# arduinoFMShield.net
KiCad netlist of a schematic drawn in EAGLE
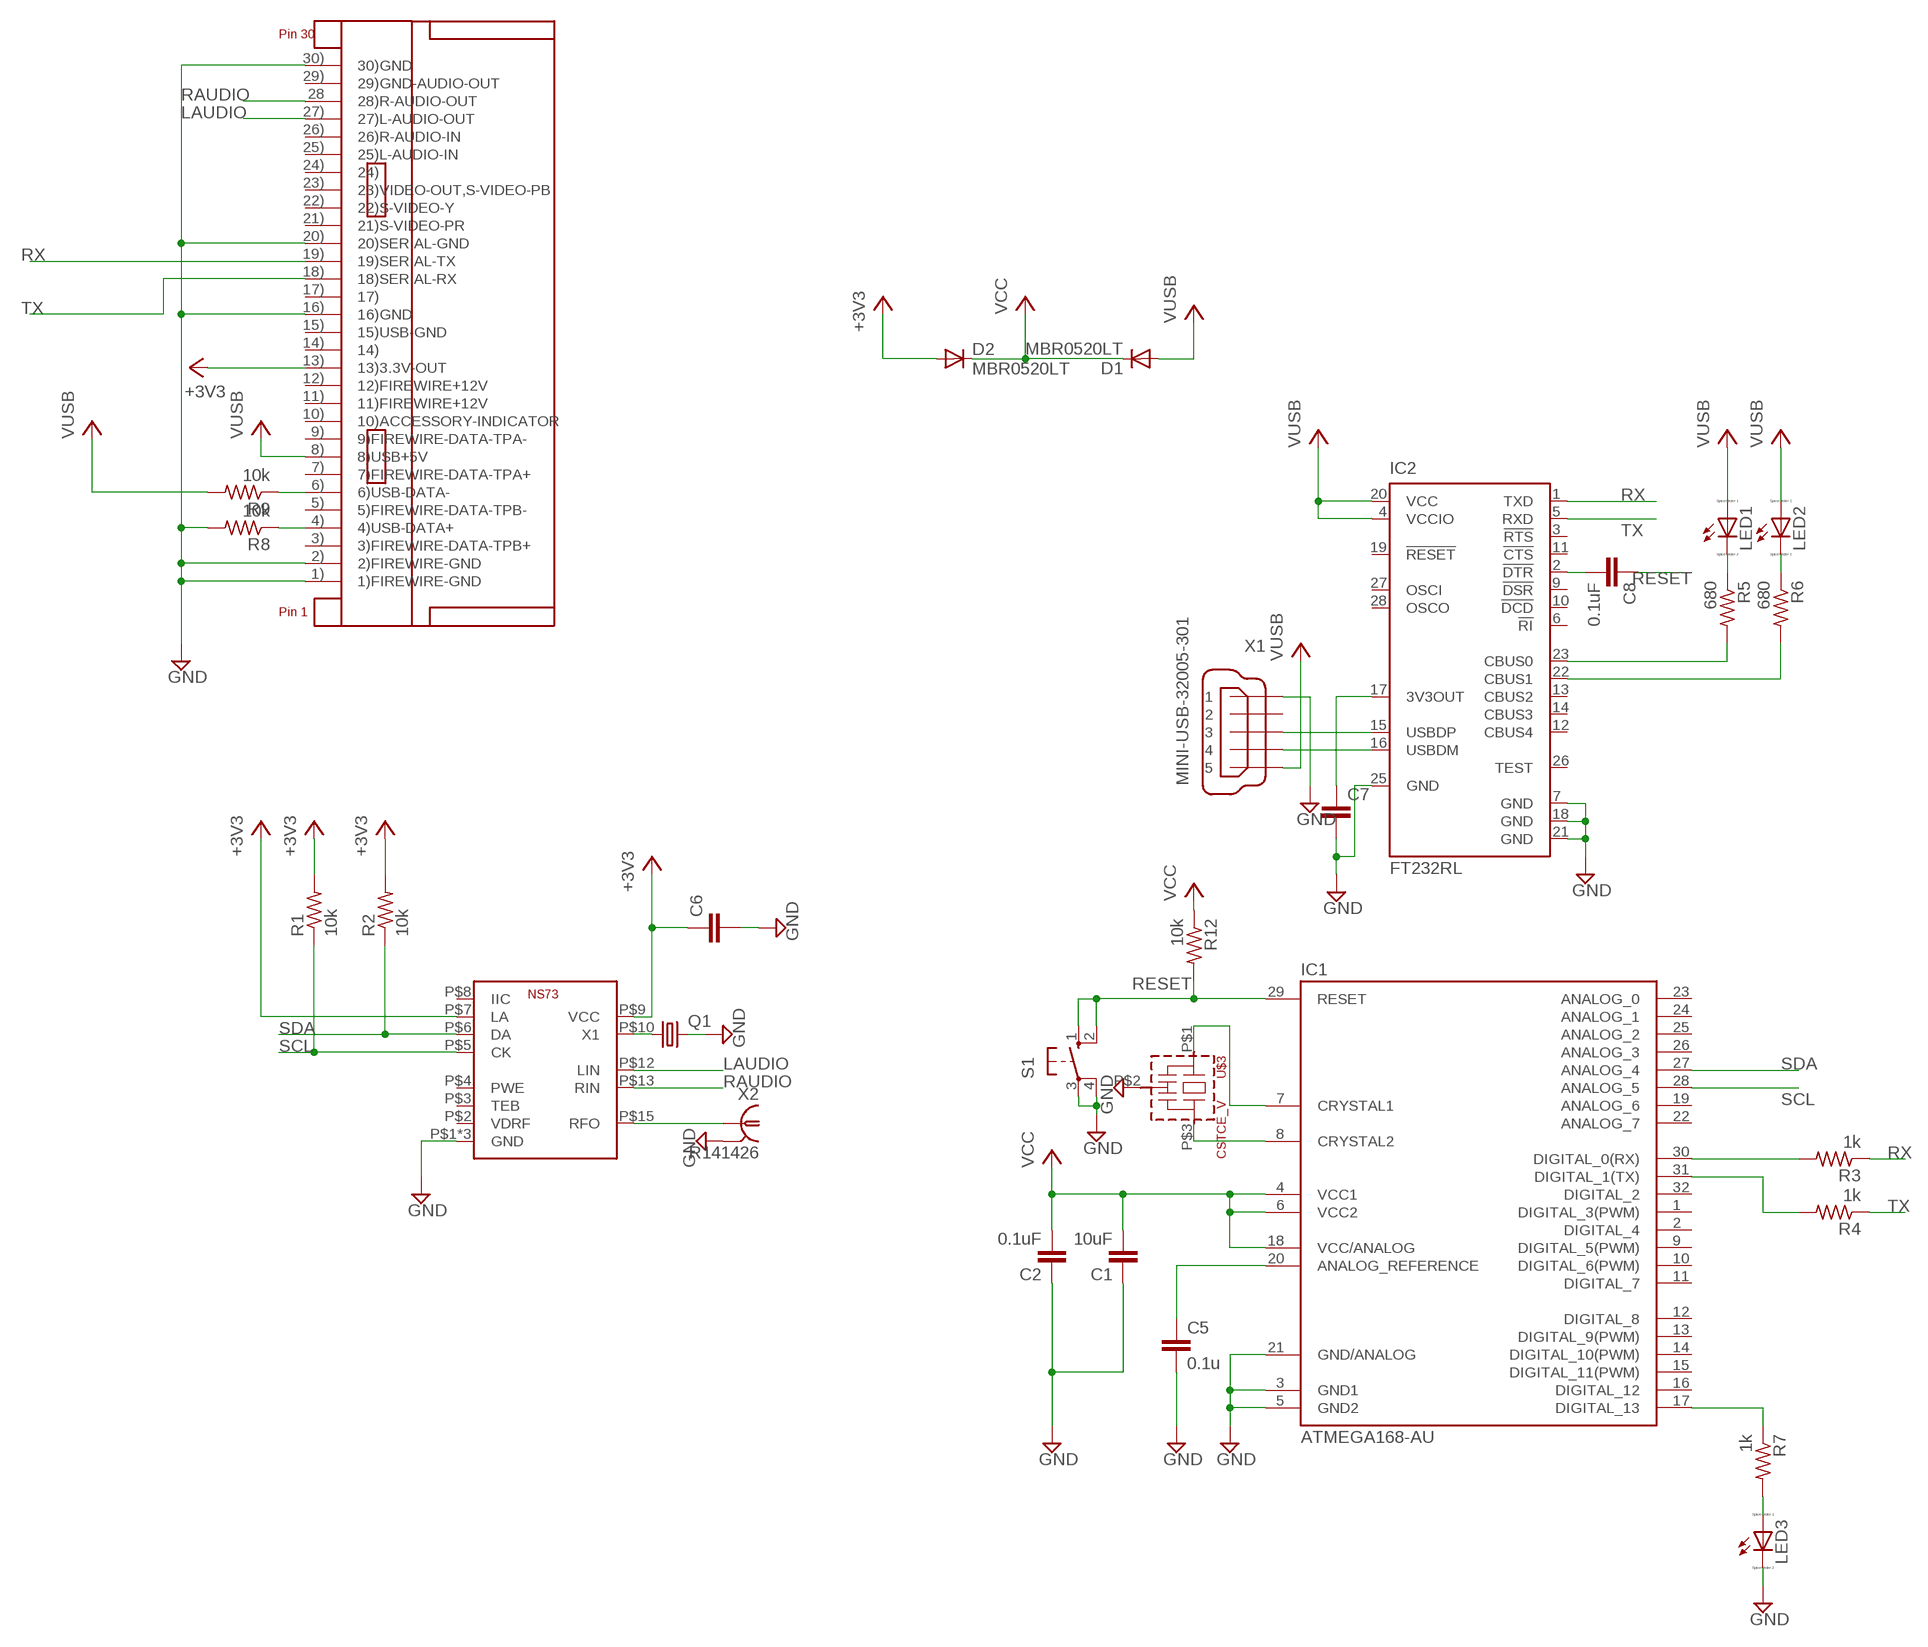
[diagram p0: schematic, sheet 1]

(export (version "E")
  (design (tool "Eeschema 10.0.6"))
  (components
    (comp (ref "C1")
      (value "10uF")
      (footprint "eagle-import:C1206")
      (libsource (lib "eagle-import") (part "C-EUC1206"))
    )
    (comp (ref "C2")
      (value "0.1uF")
      (footprint "eagle-import:C1206")
      (libsource (lib "eagle-import") (part "C-EUC1206"))
    )
    (comp (ref "C5")
      (value "0.1u")
      (footprint "eagle-import:C1206")
      (libsource (lib "eagle-import") (part "C-EUC1206"))
    )
    (comp (ref "C6")
      (value "C-EUC1206")
      (footprint "eagle-import:C1206")
      (libsource (lib "eagle-import") (part "C-EUC1206"))
    )
    (comp (ref "C7")
      (value "C-EUC1206")
      (footprint "eagle-import:C1206")
      (libsource (lib "eagle-import") (part "C-EUC1206"))
    )
    (comp (ref "C8")
      (value "0.1uF")
      (footprint "eagle-import:C1206")
      (libsource (lib "eagle-import") (part "C-EUC1206"))
    )
    (comp (ref "D1")
      (value "MBR0520LT")
      (footprint "eagle-import:SOD123")
      (libsource (lib "eagle-import") (part "MBR0520LT"))
    )
    (comp (ref "D2")
      (value "MBR0520LT")
      (footprint "eagle-import:SOD123")
      (libsource (lib "eagle-import") (part "MBR0520LT"))
    )
    (comp (ref "IC1")
      (value "ATMEGA168-AU")
      (footprint "eagle-import:TQFP32-08")
      (libsource (lib "eagle-import") (part "ATMEGA168-AU"))
    )
    (comp (ref "IC2")
      (value "FT232RL")
      (footprint "eagle-import:SSOP28")
      (libsource (lib "eagle-import") (part "FT232RL"))
    )
    (comp (ref "LED1")
      (value "LED_ESML0603")
      (footprint "eagle-import:LED_SML0603")
      (libsource (lib "eagle-import") (part "LED_ESML0603"))
    )
    (comp (ref "LED2")
      (value "LED_ESML0603")
      (footprint "eagle-import:LED_SML0603")
      (libsource (lib "eagle-import") (part "LED_ESML0603"))
    )
    (comp (ref "LED3")
      (value "LED_ESML0603")
      (footprint "eagle-import:LED_SML0603")
      (libsource (lib "eagle-import") (part "LED_ESML0603"))
    )
    (comp (ref "Q1")
      (value "CRYSTALTC26H")
      (footprint "eagle-import:TC26H")
      (libsource (lib "eagle-import") (part "CRYSTALTC26H"))
    )
    (comp (ref "R1")
      (value "10k")
      (footprint "eagle-import:R1206")
      (libsource (lib "eagle-import") (part "R-US_R1206"))
    )
    (comp (ref "R2")
      (value "10k")
      (footprint "eagle-import:R1206")
      (libsource (lib "eagle-import") (part "R-US_R1206"))
    )
    (comp (ref "R3")
      (value "1k")
      (footprint "eagle-import:R1206")
      (libsource (lib "eagle-import") (part "R-US_R1206"))
    )
    (comp (ref "R4")
      (value "1k")
      (footprint "eagle-import:R1206")
      (libsource (lib "eagle-import") (part "R-US_R1206"))
    )
    (comp (ref "R5")
      (value "680")
      (footprint "eagle-import:R0805")
      (libsource (lib "eagle-import") (part "R-US_R0805"))
    )
    (comp (ref "R6")
      (value "680")
      (footprint "eagle-import:R0805")
      (libsource (lib "eagle-import") (part "R-US_R0805"))
    )
    (comp (ref "R7")
      (value "1k")
      (footprint "eagle-import:R1206")
      (libsource (lib "eagle-import") (part "R-US_R1206"))
    )
    (comp (ref "R8")
      (value "10k")
      (footprint "eagle-import:R1206")
      (libsource (lib "eagle-import") (part "R-US_R1206"))
    )
    (comp (ref "R9")
      (value "10k")
      (footprint "eagle-import:R1206")
      (libsource (lib "eagle-import") (part "R-US_R1206"))
    )
    (comp (ref "R12")
      (value "10k")
      (footprint "eagle-import:R1206")
      (libsource (lib "eagle-import") (part "R-US_R1206"))
    )
    (comp (ref "S1")
      (value "10-XX")
      (footprint "eagle-import:B3F-10XX")
      (fields (field (name "MPN") "B3F-1000"))
      (libsource (lib "eagle-import") (part "10-XX"))
    )
    (comp (ref "U$1")
      (value "NS73")
      (footprint "eagle-import:NS73")
      (libsource (lib "eagle-import") (part "NS73"))
    )
    (comp (ref "U$2")
      (value "IPOD-DOCK-CONNECTOR")
      (footprint "eagle-import:IPOD_CONNECTOR")
      (libsource (lib "eagle-import") (part "IPOD-DOCK-CONNECTOR"))
    )
    (comp (ref "U$3")
      (value "CSTCE_V")
      (footprint "eagle-import:CSTCE_V")
      (libsource (lib "eagle-import") (part "CSTCE_V"))
    )
    (comp (ref "X1")
      (value "MINI-USB-32005-301")
      (footprint "eagle-import:32005-301")
      (libsource (lib "eagle-import") (part "MINI-USB-32005-301"))
    )
    (comp (ref "X2")
      (value "R141426")
      (footprint "eagle-import:R141426")
      (fields (field (name "MF") "FARNELL") (field (name "MPN") "R141426161"))
      (libsource (lib "eagle-import") (part "R141426"))
    )
  )
  (nets
    (net (code "1") (name "+3V3") (class "Default")
      (node (ref "C6") (pin "1") (pinfunction "1_1") (pintype "passive"))
      (node (ref "D2") (pin "A") (pinfunction "A_A") (pintype "passive"))
      (node (ref "R1") (pin "2") (pinfunction "2_2") (pintype "passive"))
      (node (ref "R2") (pin "2") (pinfunction "2_2") (pintype "passive"))
      (node (ref "U$1") (pin "P$7") (pinfunction "LA_P$7") (pintype "bidirectional"))
      (node (ref "U$1") (pin "P$9") (pinfunction "VCC_P$9") (pintype "bidirectional"))
      (node (ref "U$2") (pin "13)") (pinfunction "13)3.3V-OUT_13)") (pintype "bidirectional"))
    )
    (net (code "2") (name "/LAUDIO") (class "Default")
      (node (ref "U$1") (pin "P$12") (pinfunction "LIN_P$12") (pintype "bidirectional"))
      (node (ref "U$2") (pin "27)") (pinfunction "27)L-AUDIO-OUT_27)") (pintype "bidirectional"))
    )
    (net (code "3") (name "/RAUDIO") (class "Default")
      (node (ref "U$1") (pin "P$13") (pinfunction "RIN_P$13") (pintype "bidirectional"))
      (node (ref "U$2") (pin "28") (pinfunction "28)R-AUDIO-OUT_28") (pintype "bidirectional"))
    )
    (net (code "4") (name "/RESET") (class "Default")
      (node (ref "C8") (pin "1") (pinfunction "1_1") (pintype "passive"))
      (node (ref "IC1") (pin "29") (pinfunction "RESET_29") (pintype "bidirectional"))
      (node (ref "R12") (pin "2") (pinfunction "2_2") (pintype "passive"))
      (node (ref "S1") (pin "1") (pinfunction "S_1") (pintype "passive"))
      (node (ref "S1") (pin "2") (pinfunction "S1_2") (pintype "passive"))
    )
    (net (code "5") (name "/RX") (class "Default")
      (node (ref "IC2") (pin "1") (pinfunction "TXD_1") (pintype "output"))
      (node (ref "R3") (pin "1") (pinfunction "1_1") (pintype "passive"))
      (node (ref "U$2") (pin "19)") (pinfunction "19)SERIAL-TX_19)") (pintype "bidirectional"))
    )
    (net (code "6") (name "/SCL") (class "Default")
      (node (ref "IC1") (pin "28") (pinfunction "ANALOG_5_28") (pintype "bidirectional"))
      (node (ref "R1") (pin "1") (pinfunction "1_1") (pintype "passive"))
      (node (ref "U$1") (pin "P$5") (pinfunction "CK_P$5") (pintype "bidirectional"))
    )
    (net (code "7") (name "/SDA") (class "Default")
      (node (ref "IC1") (pin "27") (pinfunction "ANALOG_4_27") (pintype "bidirectional"))
      (node (ref "R2") (pin "1") (pinfunction "1_1") (pintype "passive"))
      (node (ref "U$1") (pin "P$6") (pinfunction "DA_P$6") (pintype "bidirectional"))
    )
    (net (code "8") (name "/TX") (class "Default")
      (node (ref "IC2") (pin "5") (pinfunction "RXD_5") (pintype "input"))
      (node (ref "R4") (pin "1") (pinfunction "1_1") (pintype "passive"))
      (node (ref "U$2") (pin "18)") (pinfunction "18)SERIAL-RX_18)") (pintype "bidirectional"))
    )
    (net (code "9") (name "GND") (class "Default")
      (node (ref "C1") (pin "1") (pinfunction "1_1") (pintype "passive"))
      (node (ref "C2") (pin "1") (pinfunction "1_1") (pintype "passive"))
      (node (ref "C5") (pin "2") (pinfunction "2_2") (pintype "passive"))
      (node (ref "C6") (pin "2") (pinfunction "2_2") (pintype "passive"))
      (node (ref "C7") (pin "2") (pinfunction "2_2") (pintype "passive"))
      (node (ref "IC1") (pin "21") (pinfunction "GND/ANALOG_21") (pintype "power_in"))
      (node (ref "IC1") (pin "3") (pinfunction "GND1_3") (pintype "power_in"))
      (node (ref "IC1") (pin "5") (pinfunction "GND2_5") (pintype "power_in"))
      (node (ref "IC2") (pin "18") (pinfunction "GND_18") (pintype "power_in"))
      (node (ref "IC2") (pin "21") (pinfunction "GND_21") (pintype "power_in"))
      (node (ref "IC2") (pin "25") (pinfunction "GND_25") (pintype "power_in"))
      (node (ref "IC2") (pin "7") (pinfunction "GND_7") (pintype "power_in"))
      (node (ref "LED3") (pin "C") (pinfunction "C_C") (pintype "passive"))
      (node (ref "Q1") (pin "2") (pinfunction "2_2") (pintype "passive"))
      (node (ref "R8") (pin "2") (pinfunction "2_2") (pintype "passive"))
      (node (ref "S1") (pin "3") (pinfunction "P_3") (pintype "passive"))
      (node (ref "S1") (pin "4") (pinfunction "P1_4") (pintype "passive"))
      (node (ref "U$1") (pin "P$1") (pinfunction "GND_P$1") (pintype "bidirectional"))
      (node (ref "U$1") (pin "P$11") (pinfunction "GND_P$11") (pintype "bidirectional"))
      (node (ref "U$1") (pin "P$14") (pinfunction "GND_P$14") (pintype "bidirectional"))
      (node (ref "U$2") (pin "1)") (pinfunction "1)FIREWIRE-GND_1)") (pintype "bidirectional"))
      (node (ref "U$2") (pin "16)") (pinfunction "16)GND_16)") (pintype "bidirectional"))
      (node (ref "U$2") (pin "2)") (pinfunction "2)FIREWIRE-GND_2)") (pintype "bidirectional"))
      (node (ref "U$2") (pin "20)") (pinfunction "20)SERIAL-GND_20)") (pintype "bidirectional"))
      (node (ref "U$2") (pin "30)") (pinfunction "30)GND_30)") (pintype "bidirectional"))
      (node (ref "U$3") (pin "P$2") (pinfunction "VSS_P$2") (pintype "power_in"))
      (node (ref "X1") (pin "1") (pinfunction "1_1") (pintype "passive"))
      (node (ref "X2") (pin "2") (pinfunction "2_2") (pintype "passive"))
      (node (ref "X2") (pin "3") (pinfunction "2_3") (pintype "passive"))
      (node (ref "X2") (pin "4") (pinfunction "2_4") (pintype "passive"))
      (node (ref "X2") (pin "5") (pinfunction "2_5") (pintype "passive"))
    )
    (net (code "10") (name "Net-(IC1-ANALOG_REFERENCE)") (class "Default")
      (node (ref "C5") (pin "1") (pinfunction "1_1") (pintype "passive"))
      (node (ref "IC1") (pin "20") (pinfunction "ANALOG_REFERENCE_20") (pintype "passive"))
    )
    (net (code "11") (name "Net-(IC1-CRYSTAL1)") (class "Default")
      (node (ref "IC1") (pin "7") (pinfunction "CRYSTAL1_7") (pintype "bidirectional"))
      (node (ref "U$3") (pin "P$1") (pinfunction "1_P$1") (pintype "output"))
    )
    (net (code "12") (name "Net-(IC1-CRYSTAL2)") (class "Default")
      (node (ref "IC1") (pin "8") (pinfunction "CRYSTAL2_8") (pintype "bidirectional"))
      (node (ref "U$3") (pin "P$3") (pinfunction "3_P$3") (pintype "input"))
    )
    (net (code "13") (name "Net-(IC1-DIGITAL_0(RX))") (class "Default")
      (node (ref "IC1") (pin "30") (pinfunction "DIGITAL_0(RX)_30") (pintype "bidirectional"))
      (node (ref "R3") (pin "2") (pinfunction "2_2") (pintype "passive"))
    )
    (net (code "14") (name "Net-(IC1-DIGITAL_1(TX))") (class "Default")
      (node (ref "IC1") (pin "31") (pinfunction "DIGITAL_1(TX)_31") (pintype "bidirectional"))
      (node (ref "R4") (pin "2") (pinfunction "2_2") (pintype "passive"))
    )
    (net (code "15") (name "Net-(IC1-DIGITAL_13)") (class "Default")
      (node (ref "IC1") (pin "17") (pinfunction "DIGITAL_13_17") (pintype "bidirectional"))
      (node (ref "R7") (pin "1") (pinfunction "1_1") (pintype "passive"))
    )
    (net (code "16") (name "Net-(IC2-3V3OUT)") (class "Default")
      (node (ref "C7") (pin "1") (pinfunction "1_1") (pintype "passive"))
      (node (ref "IC2") (pin "17") (pinfunction "3V3OUT_17") (pintype "output"))
    )
    (net (code "17") (name "Net-(IC2-CBUS0)") (class "Default")
      (node (ref "IC2") (pin "23") (pinfunction "CBUS0_23") (pintype "bidirectional"))
      (node (ref "R5") (pin "2") (pinfunction "2_2") (pintype "passive"))
    )
    (net (code "18") (name "Net-(IC2-CBUS1)") (class "Default")
      (node (ref "IC2") (pin "22") (pinfunction "CBUS1_22") (pintype "bidirectional"))
      (node (ref "R6") (pin "2") (pinfunction "2_2") (pintype "passive"))
    )
    (net (code "19") (name "Net-(IC2-USBDM)") (class "Default")
      (node (ref "IC2") (pin "16") (pinfunction "USBDM_16") (pintype "bidirectional"))
      (node (ref "X1") (pin "4") (pinfunction "4_4") (pintype "passive"))
    )
    (net (code "20") (name "Net-(IC2-USBDP)") (class "Default")
      (node (ref "IC2") (pin "15") (pinfunction "USBDP_15") (pintype "bidirectional"))
      (node (ref "X1") (pin "3") (pinfunction "3_3") (pintype "passive"))
    )
    (net (code "21") (name "Net-(IC2-~{DTR})") (class "Default")
      (node (ref "C8") (pin "2") (pinfunction "2_2") (pintype "passive"))
      (node (ref "IC2") (pin "2") (pinfunction "~{DTR}_2") (pintype "output"))
    )
    (net (code "22") (name "Net-(LED1-PadC)") (class "Default")
      (node (ref "LED1") (pin "C") (pinfunction "C_C") (pintype "passive"))
      (node (ref "R5") (pin "1") (pinfunction "1_1") (pintype "passive"))
    )
    (net (code "23") (name "Net-(LED2-PadC)") (class "Default")
      (node (ref "LED2") (pin "C") (pinfunction "C_C") (pintype "passive"))
      (node (ref "R6") (pin "1") (pinfunction "1_1") (pintype "passive"))
    )
    (net (code "24") (name "Net-(LED3-PadA)") (class "Default")
      (node (ref "LED3") (pin "A") (pinfunction "A_A") (pintype "passive"))
      (node (ref "R7") (pin "2") (pinfunction "2_2") (pintype "passive"))
    )
    (net (code "25") (name "Net-(U$1-RFO)") (class "Default")
      (node (ref "U$1") (pin "P$15") (pinfunction "RFO_P$15") (pintype "bidirectional"))
      (node (ref "X2") (pin "1") (pinfunction "1_1") (pintype "passive"))
    )
    (net (code "26") (name "Net-(U$1-X1)") (class "Default")
      (node (ref "Q1") (pin "1") (pinfunction "1_1") (pintype "passive"))
      (node (ref "U$1") (pin "P$10") (pinfunction "X1_P$10") (pintype "bidirectional"))
    )
    (net (code "27") (name "Net-(U$2-4)USB-DATA+)") (class "Default")
      (node (ref "R8") (pin "1") (pinfunction "1_1") (pintype "passive"))
      (node (ref "U$2") (pin "4)") (pinfunction "4)USB-DATA+_4)") (pintype "bidirectional"))
    )
    (net (code "28") (name "Net-(U$2-6)USB-DATA-)") (class "Default")
      (node (ref "R9") (pin "1") (pinfunction "1_1") (pintype "passive"))
      (node (ref "U$2") (pin "6)") (pinfunction "6)USB-DATA-_6)") (pintype "bidirectional"))
    )
    (net (code "29") (name "VCC") (class "Default")
      (node (ref "C1") (pin "2") (pinfunction "2_2") (pintype "passive"))
      (node (ref "C2") (pin "2") (pinfunction "2_2") (pintype "passive"))
      (node (ref "D1") (pin "C") (pinfunction "C_C") (pintype "passive"))
      (node (ref "D2") (pin "C") (pinfunction "C_C") (pintype "passive"))
      (node (ref "IC1") (pin "18") (pinfunction "VCC/ANALOG_18") (pintype "passive"))
      (node (ref "IC1") (pin "4") (pinfunction "VCC1_4") (pintype "power_in"))
      (node (ref "IC1") (pin "6") (pinfunction "VCC2_6") (pintype "power_in"))
      (node (ref "R12") (pin "1") (pinfunction "1_1") (pintype "passive"))
    )
    (net (code "30") (name "VUSB") (class "Default")
      (node (ref "D1") (pin "A") (pinfunction "A_A") (pintype "passive"))
      (node (ref "IC2") (pin "20") (pinfunction "VCC_20") (pintype "power_in"))
      (node (ref "IC2") (pin "4") (pinfunction "VCCIO_4") (pintype "power_in"))
      (node (ref "LED1") (pin "A") (pinfunction "A_A") (pintype "passive"))
      (node (ref "LED2") (pin "A") (pinfunction "A_A") (pintype "passive"))
      (node (ref "R9") (pin "2") (pinfunction "2_2") (pintype "passive"))
      (node (ref "U$2") (pin "8)") (pinfunction "8)USB+5V_8)") (pintype "bidirectional"))
      (node (ref "X1") (pin "5") (pinfunction "5_5") (pintype "passive"))
    )
    (net (code "31") (name "unconnected-(IC1-ANALOG_0-Pad23)") (class "Default")
      (node (ref "IC1") (pin "23") (pinfunction "ANALOG_0_23") (pintype "bidirectional"))
    )
    (net (code "32") (name "unconnected-(IC1-ANALOG_1-Pad24)") (class "Default")
      (node (ref "IC1") (pin "24") (pinfunction "ANALOG_1_24") (pintype "bidirectional"))
    )
    (net (code "33") (name "unconnected-(IC1-ANALOG_2-Pad25)") (class "Default")
      (node (ref "IC1") (pin "25") (pinfunction "ANALOG_2_25") (pintype "bidirectional"))
    )
    (net (code "34") (name "unconnected-(IC1-ANALOG_3-Pad26)") (class "Default")
      (node (ref "IC1") (pin "26") (pinfunction "ANALOG_3_26") (pintype "bidirectional"))
    )
    (net (code "35") (name "unconnected-(IC1-ANALOG_6-Pad19)") (class "Default")
      (node (ref "IC1") (pin "19") (pinfunction "ANALOG_6_19") (pintype "passive"))
    )
    (net (code "36") (name "unconnected-(IC1-ANALOG_7-Pad22)") (class "Default")
      (node (ref "IC1") (pin "22") (pinfunction "ANALOG_7_22") (pintype "passive"))
    )
    (net (code "37") (name "unconnected-(IC1-DIGITAL_2-Pad32)") (class "Default")
      (node (ref "IC1") (pin "32") (pinfunction "DIGITAL_2_32") (pintype "bidirectional"))
    )
    (net (code "38") (name "unconnected-(IC1-DIGITAL_3(PWM)-Pad1)") (class "Default")
      (node (ref "IC1") (pin "1") (pinfunction "DIGITAL_3(PWM)_1") (pintype "bidirectional"))
    )
    (net (code "39") (name "unconnected-(IC1-DIGITAL_4-Pad2)") (class "Default")
      (node (ref "IC1") (pin "2") (pinfunction "DIGITAL_4_2") (pintype "bidirectional"))
    )
    (net (code "40") (name "unconnected-(IC1-DIGITAL_5(PWM)-Pad9)") (class "Default")
      (node (ref "IC1") (pin "9") (pinfunction "DIGITAL_5(PWM)_9") (pintype "bidirectional"))
    )
    (net (code "41") (name "unconnected-(IC1-DIGITAL_6(PWM)-Pad10)") (class "Default")
      (node (ref "IC1") (pin "10") (pinfunction "DIGITAL_6(PWM)_10") (pintype "bidirectional"))
    )
    (net (code "42") (name "unconnected-(IC1-DIGITAL_7-Pad11)") (class "Default")
      (node (ref "IC1") (pin "11") (pinfunction "DIGITAL_7_11") (pintype "bidirectional"))
    )
    (net (code "43") (name "unconnected-(IC1-DIGITAL_8-Pad12)") (class "Default")
      (node (ref "IC1") (pin "12") (pinfunction "DIGITAL_8_12") (pintype "bidirectional"))
    )
    (net (code "44") (name "unconnected-(IC1-DIGITAL_9(PWM)-Pad13)") (class "Default")
      (node (ref "IC1") (pin "13") (pinfunction "DIGITAL_9(PWM)_13") (pintype "bidirectional"))
    )
    (net (code "45") (name "unconnected-(IC1-DIGITAL_10(PWM)-Pad14)") (class "Default")
      (node (ref "IC1") (pin "14") (pinfunction "DIGITAL_10(PWM)_14") (pintype "bidirectional"))
    )
    (net (code "46") (name "unconnected-(IC1-DIGITAL_11(PWM)-Pad15)") (class "Default")
      (node (ref "IC1") (pin "15") (pinfunction "DIGITAL_11(PWM)_15") (pintype "bidirectional"))
    )
    (net (code "47") (name "unconnected-(IC1-DIGITAL_12-Pad16)") (class "Default")
      (node (ref "IC1") (pin "16") (pinfunction "DIGITAL_12_16") (pintype "bidirectional"))
    )
    (net (code "48") (name "unconnected-(IC2-CBUS2-Pad13)") (class "Default")
      (node (ref "IC2") (pin "13") (pinfunction "CBUS2_13") (pintype "bidirectional"))
    )
    (net (code "49") (name "unconnected-(IC2-CBUS3-Pad14)") (class "Default")
      (node (ref "IC2") (pin "14") (pinfunction "CBUS3_14") (pintype "bidirectional"))
    )
    (net (code "50") (name "unconnected-(IC2-CBUS4-Pad12)") (class "Default")
      (node (ref "IC2") (pin "12") (pinfunction "CBUS4_12") (pintype "bidirectional"))
    )
    (net (code "51") (name "unconnected-(IC2-OSCI-Pad27)") (class "Default")
      (node (ref "IC2") (pin "27") (pinfunction "OSCI_27") (pintype "input"))
    )
    (net (code "52") (name "unconnected-(IC2-OSCO-Pad28)") (class "Default")
      (node (ref "IC2") (pin "28") (pinfunction "OSCO_28") (pintype "output"))
    )
    (net (code "53") (name "unconnected-(IC2-TEST-Pad26)") (class "Default")
      (node (ref "IC2") (pin "26") (pinfunction "TEST_26") (pintype "input"))
    )
    (net (code "54") (name "unconnected-(IC2-~{CTS}-Pad11)") (class "Default")
      (node (ref "IC2") (pin "11") (pinfunction "~{CTS}_11") (pintype "input"))
    )
    (net (code "55") (name "unconnected-(IC2-~{DCD}-Pad10)") (class "Default")
      (node (ref "IC2") (pin "10") (pinfunction "~{DCD}_10") (pintype "input"))
    )
    (net (code "56") (name "unconnected-(IC2-~{DSR}-Pad9)") (class "Default")
      (node (ref "IC2") (pin "9") (pinfunction "~{DSR}_9") (pintype "input"))
    )
    (net (code "57") (name "unconnected-(IC2-~{RESET}-Pad19)") (class "Default")
      (node (ref "IC2") (pin "19") (pinfunction "~{RESET}_19") (pintype "input"))
    )
    (net (code "58") (name "unconnected-(IC2-~{RI}-Pad6)") (class "Default")
      (node (ref "IC2") (pin "6") (pinfunction "~{RI}_6") (pintype "input"))
    )
    (net (code "59") (name "unconnected-(IC2-~{RTS}-Pad3)") (class "Default")
      (node (ref "IC2") (pin "3") (pinfunction "~{RTS}_3") (pintype "output"))
    )
    (net (code "60") (name "unconnected-(U$1-IIC-PadP$8)") (class "Default")
      (node (ref "U$1") (pin "P$8") (pinfunction "IIC_P$8") (pintype "bidirectional"))
    )
    (net (code "61") (name "unconnected-(U$1-PWE-PadP$4)") (class "Default")
      (node (ref "U$1") (pin "P$4") (pinfunction "PWE_P$4") (pintype "bidirectional"))
    )
    (net (code "62") (name "unconnected-(U$1-TEB-PadP$3)") (class "Default")
      (node (ref "U$1") (pin "P$3") (pinfunction "TEB_P$3") (pintype "bidirectional"))
    )
    (net (code "63") (name "unconnected-(U$1-VDRF-PadP$2)") (class "Default")
      (node (ref "U$1") (pin "P$2") (pinfunction "VDRF_P$2") (pintype "bidirectional"))
    )
    (net (code "64") (name "unconnected-(U$2-3)FIREWIRE-DATA-TPB+-Pad3))") (class "Default")
      (node (ref "U$2") (pin "3)") (pinfunction "3)FIREWIRE-DATA-TPB+_3)") (pintype "bidirectional"))
    )
    (net (code "65") (name "unconnected-(U$2-5)FIREWIRE-DATA-TPB--Pad5))") (class "Default")
      (node (ref "U$2") (pin "5)") (pinfunction "5)FIREWIRE-DATA-TPB-_5)") (pintype "bidirectional"))
    )
    (net (code "66") (name "unconnected-(U$2-7)FIREWIRE-DATA-TPA+-Pad7))") (class "Default")
      (node (ref "U$2") (pin "7)") (pinfunction "7)FIREWIRE-DATA-TPA+_7)") (pintype "bidirectional"))
    )
    (net (code "67") (name "unconnected-(U$2-9)FIREWIRE-DATA-TPA--Pad9))") (class "Default")
      (node (ref "U$2") (pin "9)") (pinfunction "9)FIREWIRE-DATA-TPA-_9)") (pintype "bidirectional"))
    )
    (net (code "68") (name "unconnected-(U$2-10)ACCESSORY-INDICATOR-Pad10))") (class "Default")
      (node (ref "U$2") (pin "10)") (pinfunction "10)ACCESSORY-INDICATOR_10)") (pintype "bidirectional"))
    )
    (net (code "69") (name "unconnected-(U$2-11)FIREWIRE+12V-Pad11))") (class "Default")
      (node (ref "U$2") (pin "11)") (pinfunction "11)FIREWIRE+12V_11)") (pintype "bidirectional"))
    )
    (net (code "70") (name "unconnected-(U$2-12)FIREWIRE+12V-Pad12))") (class "Default")
      (node (ref "U$2") (pin "12)") (pinfunction "12)FIREWIRE+12V_12)") (pintype "bidirectional"))
    )
    (net (code "71") (name "unconnected-(U$2-15)USB-GND-Pad15))") (class "Default")
      (node (ref "U$2") (pin "15)") (pinfunction "15)USB-GND_15)") (pintype "bidirectional"))
    )
    (net (code "72") (name "unconnected-(U$2-21)S-VIDEO-PR-Pad21))") (class "Default")
      (node (ref "U$2") (pin "21)") (pinfunction "21)S-VIDEO-PR_21)") (pintype "bidirectional"))
    )
    (net (code "73") (name "unconnected-(U$2-22)S-VIDEO-Y-Pad22))") (class "Default")
      (node (ref "U$2") (pin "22)") (pinfunction "22)S-VIDEO-Y_22)") (pintype "bidirectional"))
    )
    (net (code "74") (name "unconnected-(U$2-23)VIDEO-OUT,S-VIDEO-PB-Pad23))") (class "Default")
      (node (ref "U$2") (pin "23)") (pinfunction "23)VIDEO-OUT,S-VIDEO-PB_23)") (pintype "bidirectional"))
    )
    (net (code "75") (name "unconnected-(U$2-25)L-AUDIO-IN-Pad25))") (class "Default")
      (node (ref "U$2") (pin "25)") (pinfunction "25)L-AUDIO-IN_25)") (pintype "bidirectional"))
    )
    (net (code "76") (name "unconnected-(U$2-26)R-AUDIO-IN-Pad26))") (class "Default")
      (node (ref "U$2") (pin "26)") (pinfunction "26)R-AUDIO-IN_26)") (pintype "bidirectional"))
    )
    (net (code "77") (name "unconnected-(U$2-29)GND-AUDIO-OUT-Pad29))") (class "Default")
      (node (ref "U$2") (pin "29)") (pinfunction "29)GND-AUDIO-OUT_29)") (pintype "bidirectional"))
    )
    (net (code "78") (name "unconnected-(U$2-Pad14))") (class "Default")
      (node (ref "U$2") (pin "14)") (pinfunction "14)_14)") (pintype "bidirectional"))
    )
    (net (code "79") (name "unconnected-(U$2-Pad17))") (class "Default")
      (node (ref "U$2") (pin "17)") (pinfunction "17)_17)") (pintype "bidirectional"))
    )
    (net (code "80") (name "unconnected-(U$2-Pad24))") (class "Default")
      (node (ref "U$2") (pin "24)") (pinfunction "24)_24)") (pintype "bidirectional"))
    )
    (net (code "81") (name "unconnected-(X1-Pad2)") (class "Default")
      (node (ref "X1") (pin "2") (pinfunction "2_2") (pintype "passive"))
    )
  )
)
